# SiPD_Design.net
KiCad netlist of a schematic drawn in Altium Designer
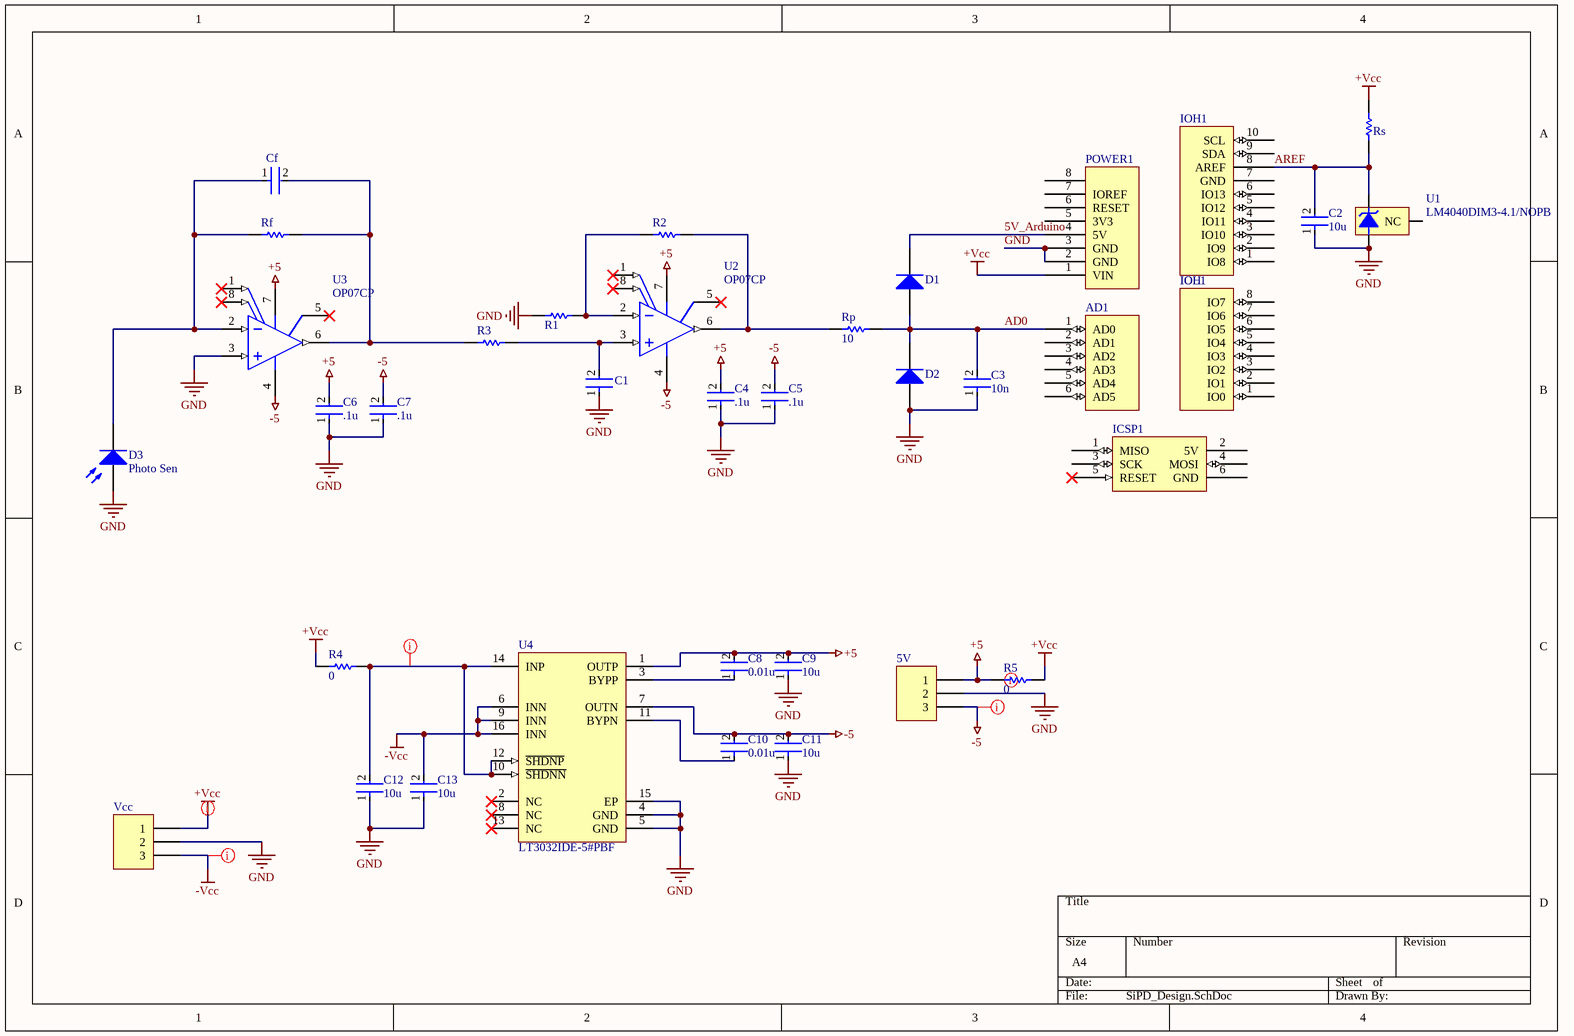
[diagram p0: SiPD_Design.SchDoc]

(export (version "E")
  (design (tool "Eeschema 10.0.6"))
  (components
    (comp (ref "5V")
      (value "5V")
      (footprint "HDR1X3")
      (description "Header, 3-Pin")
      (fields (field (name "PUBLISHER") "Altium Limited"))
      (libsource (lib "Miscellaneous Connectors") (part "Header 3"))
    )
    (comp (ref "AD1")
      (value "AD")
      (footprint "Header:Header 6x1 8.5mm")
      (libsource (lib "Header") (part "AD"))
    )
    (comp (ref "C1")
      (value "~")
      (footprint "FP-C0805C-DG-MFG")
      (description "CAP CER 10UF 10V X5R 0805")
      (fields (field (name "TOLERANCE") "10%") (field (name "MANUFACTURER PART NUMBER") "C0805C106K8PACTU"))
      (libsource (lib "Altium Content Vault") (part "11868f565c42a9108669ba33697ecf6"))
    )
    (comp (ref "C2")
      (value "10u")
      (footprint "FP-C0805C-DG-MFG")
      (description "CAP CER 10UF 10V X5R 0805")
      (fields (field (name "TOLERANCE") "10%") (field (name "MANUFACTURER PART NUMBER") "C0805C106K8PACTU"))
      (libsource (lib "Altium Content Vault") (part "11868f565c42a9108669ba33697ecf6"))
    )
    (comp (ref "C3")
      (value "10n")
      (footprint "FP-C0805C-DG-MFG")
      (description "CAP CER 10UF 10V X5R 0805")
      (fields (field (name "TOLERANCE") "10%") (field (name "MANUFACTURER PART NUMBER") "C0805C106K8PACTU"))
      (libsource (lib "Altium Content Vault") (part "11868f565c42a9108669ba33697ecf6"))
    )
    (comp (ref "C4")
      (value ".1u")
      (footprint "FP-C0805C-DG-MFG")
      (description "CAP CER 10UF 10V X5R 0805")
      (fields (field (name "TOLERANCE") "10%") (field (name "MANUFACTURER PART NUMBER") "C0805C106K8PACTU"))
      (libsource (lib "Altium Content Vault") (part "11868f565c42a9108669ba33697ecf6"))
    )
    (comp (ref "C5")
      (value ".1u")
      (footprint "FP-C0805C-DG-MFG")
      (description "CAP CER 10UF 10V X5R 0805")
      (fields (field (name "TOLERANCE") "10%") (field (name "MANUFACTURER PART NUMBER") "C0805C106K8PACTU"))
      (libsource (lib "Altium Content Vault") (part "11868f565c42a9108669ba33697ecf6"))
    )
    (comp (ref "C6")
      (value ".1u")
      (footprint "FP-C0805C-DG-MFG")
      (description "CAP CER 10UF 10V X5R 0805")
      (fields (field (name "TOLERANCE") "10%") (field (name "MANUFACTURER PART NUMBER") "C0805C106K8PACTU"))
      (libsource (lib "Altium Content Vault") (part "11868f565c42a9108669ba33697ecf6"))
    )
    (comp (ref "C7")
      (value ".1u")
      (footprint "FP-C0805C-DG-MFG")
      (description "CAP CER 10UF 10V X5R 0805")
      (fields (field (name "TOLERANCE") "10%") (field (name "MANUFACTURER PART NUMBER") "C0805C106K8PACTU"))
      (libsource (lib "Altium Content Vault") (part "11868f565c42a9108669ba33697ecf6"))
    )
    (comp (ref "C8")
      (value "0.01u")
      (footprint "FP-C0805C-DG-MFG")
      (description "CAP CER 10UF 10V X5R 0805")
      (fields (field (name "TOLERANCE") "10%") (field (name "MANUFACTURER PART NUMBER") "C0805C106K8PACTU"))
      (libsource (lib "Altium Content Vault") (part "11868f565c42a9108669ba33697ecf6"))
    )
    (comp (ref "C9")
      (value "10u")
      (footprint "FP-C0805C-DG-MFG")
      (description "CAP CER 10UF 10V X5R 0805")
      (fields (field (name "TOLERANCE") "10%") (field (name "MANUFACTURER PART NUMBER") "C0805C106K8PACTU"))
      (libsource (lib "Altium Content Vault") (part "11868f565c42a9108669ba33697ecf6"))
    )
    (comp (ref "C10")
      (value "0.01u")
      (footprint "FP-C0805C-DG-MFG")
      (description "CAP CER 10UF 10V X5R 0805")
      (fields (field (name "TOLERANCE") "10%") (field (name "MANUFACTURER PART NUMBER") "C0805C106K8PACTU"))
      (libsource (lib "Altium Content Vault") (part "11868f565c42a9108669ba33697ecf6"))
    )
    (comp (ref "C11")
      (value "10u")
      (footprint "FP-C0805C-DG-MFG")
      (description "CAP CER 10UF 10V X5R 0805")
      (fields (field (name "TOLERANCE") "10%") (field (name "MANUFACTURER PART NUMBER") "C0805C106K8PACTU"))
      (libsource (lib "Altium Content Vault") (part "11868f565c42a9108669ba33697ecf6"))
    )
    (comp (ref "C12")
      (value "10u")
      (footprint "FP-C0805C-DG-MFG")
      (description "CAP CER 10UF 10V X5R 0805")
      (fields (field (name "TOLERANCE") "10%") (field (name "MANUFACTURER PART NUMBER") "C0805C106K8PACTU"))
      (libsource (lib "Altium Content Vault") (part "11868f565c42a9108669ba33697ecf6"))
    )
    (comp (ref "C13")
      (value "10u")
      (footprint "FP-C0805C-DG-MFG")
      (description "CAP CER 10UF 10V X5R 0805")
      (fields (field (name "TOLERANCE") "10%") (field (name "MANUFACTURER PART NUMBER") "C0805C106K8PACTU"))
      (libsource (lib "Altium Content Vault") (part "11868f565c42a9108669ba33697ecf6"))
    )
    (comp (ref "Cf")
      (value "~")
      (footprint "FP-C0805C-DG-MFG")
      (description "CAP CER 10UF 10V X5R 0805")
      (fields (field (name "TOLERANCE") "10%") (field (name "MANUFACTURER PART NUMBER") "C0805C106K8PACTU"))
      (libsource (lib "Altium Content Vault") (part "11868f565c42a9108669ba33697ecf6"))
    )
    (comp (ref "D1")
      (value "Diode 1N4148")
      (footprint "DO-35")
      (description "High Conductance Fast Diode")
      (fields (field (name "PUBLISHER") "Altium Limited"))
      (libsource (lib "Miscellaneous Devices") (part "Diode 1N4148"))
    )
    (comp (ref "D2")
      (value "Diode 1N4148")
      (footprint "DO-35")
      (description "High Conductance Fast Diode")
      (fields (field (name "PUBLISHER") "Altium Limited"))
      (libsource (lib "Miscellaneous Devices") (part "Diode 1N4148"))
    )
    (comp (ref "D3")
      (value "Photo Sen")
      (footprint "PIN2")
      (description "Photosensitive Diode")
      (fields (field (name "PUBLISHER") "Altium Limited"))
      (libsource (lib "Miscellaneous Devices") (part "Photo Sen"))
    )
    (comp (ref "ICSP1") (value "ICSP") (footprint "ICSP") (libsource (lib "Header") (part "ICSP")))
    (comp (ref "IOH1")
      (value "IOH")
      (footprint "Header:Header 10x1 8.5mm")
      (libsource (lib "Header") (part "IOH"))
    )
    (comp (ref "IOL1") (value "IOL") (footprint "Header 8x1 8.5mm") (libsource (lib "Header") (part "IOL")))
    (comp (ref "POWER1")
      (value "POWER_UNO")
      (footprint "Header 8x1 8.5mm")
      (libsource (lib "Header") (part "POWER_UNO"))
    )
    (comp (ref "R1")
      (value "CRCW08050000Z0EA")
      (footprint "RESC2013X50X30LL20T20")
      (fields (field (name "MANUFACTURER") "Vishay Dale"))
      (libsource (lib "Altium Content Vault") (part "RES"))
    )
    (comp (ref "R2")
      (value "CRCW08050000Z0EA")
      (footprint "RESC2013X50X30LL20T20")
      (fields (field (name "MANUFACTURER") "Vishay Dale"))
      (libsource (lib "Altium Content Vault") (part "RES"))
    )
    (comp (ref "R3")
      (value "CRCW08050000Z0EA")
      (footprint "RESC2013X50X30LL20T20")
      (fields (field (name "MANUFACTURER") "Vishay Dale"))
      (libsource (lib "Altium Content Vault") (part "RES"))
    )
    (comp (ref "R4")
      (value "0")
      (footprint "RESC2013X50X30LL20T20")
      (fields (field (name "MANUFACTURER") "Vishay Dale") (field (name "PART NUMBER") "CRCW08050000Z0EA"))
      (libsource (lib "Altium Content Vault") (part "RES"))
    )
    (comp (ref "R5")
      (value "0")
      (footprint "RESC2013X50X30LL20T20")
      (fields (field (name "MANUFACTURER") "Vishay Dale") (field (name "PART NUMBER") "CRCW08050000Z0EA"))
      (libsource (lib "Altium Content Vault") (part "RES"))
    )
    (comp (ref "Rf")
      (value "~")
      (footprint "RESC2013X50X30LL20T20")
      (fields (field (name "MANUFACTURER") "Vishay Dale") (field (name "PART NUMBER") "CRCW08050000Z0EA"))
      (libsource (lib "Altium Content Vault") (part "RES"))
    )
    (comp (ref "Rp")
      (value "10")
      (footprint "RESC2013X50X30LL20T20")
      (fields (field (name "MANUFACTURER") "Vishay Dale") (field (name "PART NUMBER") "CRCW08050000Z0EA"))
      (libsource (lib "Altium Content Vault") (part "RES"))
    )
    (comp (ref "Rs")
      (value "CRCW08050000Z0EA")
      (footprint "RESC2013X50X30LL20T20")
      (fields (field (name "MANUFACTURER") "Vishay Dale"))
      (libsource (lib "Altium Content Vault") (part "RES"))
    )
    (comp (ref "U1")
      (value "LM4040DIM3-4.1/NOPB")
      (footprint "MF03A_N")
      (description "Precision Micropower Shunt Voltage Reference, 3-pin SOT-23, Pb-Free")
      (fields (field (name "MANUFACTURER") "National Semiconductor"))
      (libsource (lib "Altium Content Vault") (part "PM-REF-LM4040-SOT3"))
    )
    (comp (ref "U2")
      (value "OP07CP")
      (footprint "P0008A")
      (description "Low-Offset Voltage Operational Amplifier, 6 to 36 V, 0 to 70 degC, 8-pin DIP (P8), Pb-Free (RoHS)")
      (fields (field (name "MANUFACTURER") "Texas Instruments"))
      (libsource (lib "Altium Content Vault") (part "TI-OP07X-X8"))
    )
    (comp (ref "U3")
      (value "OP07CP")
      (footprint "P0008A")
      (description "Low-Offset Voltage Operational Amplifier, 6 to 36 V, 0 to 70 degC, 8-pin DIP (P8), Pb-Free (RoHS)")
      (fields (field (name "MANUFACTURER") "Texas Instruments"))
      (libsource (lib "Altium Content Vault") (part "TI-OP07X-X8"))
    )
    (comp (ref "U4")
      (value "LT3032IDE-5#PBF")
      (footprint "LT-DE14MA-14_V")
      (fields (field (name "MANUFACTURER") "Linear Technology"))
      (libsource (lib "Altium Content Vault") (part "LT-LT3032-DE14MA-14"))
    )
    (comp (ref "Vcc")
      (value "Vcc")
      (footprint "HDR1X3")
      (description "Header, 3-Pin")
      (fields (field (name "PUBLISHER") "Altium Limited"))
      (libsource (lib "Miscellaneous Connectors") (part "Header 3"))
    )
  )
  (nets
    (net (code "1") (name "+5") (class "Default")
      (node (ref "5V") (pin "1") (pinfunction "1_1") (pintype "passive"))
      (node (ref "C4") (pin "2") (pinfunction "2_2") (pintype "passive"))
      (node (ref "C6") (pin "2") (pinfunction "2_2") (pintype "passive"))
      (node (ref "C8") (pin "2") (pinfunction "2_2") (pintype "passive"))
      (node (ref "C9") (pin "2") (pinfunction "2_2") (pintype "passive"))
      (node (ref "R5") (pin "1") (pinfunction "1_1") (pintype "passive"))
      (node (ref "U2") (pin "7") (pinfunction "VCC+_7") (pintype "power_in"))
      (node (ref "U3") (pin "7") (pinfunction "VCC+_7") (pintype "power_in"))
      (node (ref "U4") (pin "1") (pinfunction "OUTP_1") (pintype "power_in"))
    )
    (net (code "2") (name "+Vcc") (class "Default")
      (node (ref "POWER1") (pin "1") (pinfunction "VIN_1") (pintype "power_in"))
      (node (ref "R4") (pin "1") (pinfunction "1_1") (pintype "passive"))
      (node (ref "R5") (pin "2") (pinfunction "2_2") (pintype "passive"))
      (node (ref "Rs") (pin "2") (pinfunction "2_2") (pintype "passive"))
      (node (ref "Vcc") (pin "1") (pinfunction "1_1") (pintype "passive"))
    )
    (net (code "3") (name "-5") (class "Default")
      (node (ref "5V") (pin "3") (pinfunction "3_3") (pintype "passive"))
      (node (ref "C10") (pin "2") (pinfunction "2_2") (pintype "passive"))
      (node (ref "C11") (pin "2") (pinfunction "2_2") (pintype "passive"))
      (node (ref "C5") (pin "2") (pinfunction "2_2") (pintype "passive"))
      (node (ref "C7") (pin "2") (pinfunction "2_2") (pintype "passive"))
      (node (ref "U2") (pin "4") (pinfunction "VCC-_4") (pintype "power_in"))
      (node (ref "U3") (pin "4") (pinfunction "VCC-_4") (pintype "power_in"))
      (node (ref "U4") (pin "7") (pinfunction "OUTN_7") (pintype "power_in"))
    )
    (net (code "4") (name "-Vcc") (class "Default")
      (node (ref "C13") (pin "2") (pinfunction "2_2") (pintype "passive"))
      (node (ref "U4") (pin "16") (pinfunction "INN_16") (pintype "power_in"))
      (node (ref "U4") (pin "6") (pinfunction "INN_6") (pintype "power_in"))
      (node (ref "U4") (pin "9") (pinfunction "INN_9") (pintype "power_in"))
      (node (ref "Vcc") (pin "3") (pinfunction "3_3") (pintype "passive"))
    )
    (net (code "5") (name "/5V_Arduino") (class "Default")
      (node (ref "D1") (pin "2") (pinfunction "K_2") (pintype "passive"))
      (node (ref "POWER1") (pin "4") (pinfunction "5V_4") (pintype "power_in"))
    )
    (net (code "6") (name "/AD0") (class "Default")
      (node (ref "AD1") (pin "1") (pinfunction "AD0_1") (pintype "bidirectional"))
      (node (ref "C3") (pin "2") (pinfunction "2_2") (pintype "passive"))
      (node (ref "D1") (pin "1") (pinfunction "A_1") (pintype "passive"))
      (node (ref "D2") (pin "2") (pinfunction "K_2") (pintype "passive"))
      (node (ref "Rp") (pin "2") (pinfunction "2_2") (pintype "passive"))
    )
    (net (code "7") (name "/AREF") (class "Default")
      (node (ref "C2") (pin "2") (pinfunction "2_2") (pintype "passive"))
      (node (ref "IOH1") (pin "8") (pinfunction "AREF_8") (pintype "passive"))
      (node (ref "Rs") (pin "1") (pinfunction "1_1") (pintype "passive"))
      (node (ref "U1") (pin "1") (pinfunction "+V_1") (pintype "passive"))
    )
    (net (code "8") (name "GND") (class "Default")
      (node (ref "5V") (pin "2") (pinfunction "2_2") (pintype "passive"))
      (node (ref "C1") (pin "1") (pinfunction "1_1") (pintype "passive"))
      (node (ref "C11") (pin "1") (pinfunction "1_1") (pintype "passive"))
      (node (ref "C12") (pin "1") (pinfunction "1_1") (pintype "passive"))
      (node (ref "C13") (pin "1") (pinfunction "1_1") (pintype "passive"))
      (node (ref "C2") (pin "1") (pinfunction "1_1") (pintype "passive"))
      (node (ref "C3") (pin "1") (pinfunction "1_1") (pintype "passive"))
      (node (ref "C4") (pin "1") (pinfunction "1_1") (pintype "passive"))
      (node (ref "C5") (pin "1") (pinfunction "1_1") (pintype "passive"))
      (node (ref "C6") (pin "1") (pinfunction "1_1") (pintype "passive"))
      (node (ref "C7") (pin "1") (pinfunction "1_1") (pintype "passive"))
      (node (ref "C9") (pin "1") (pinfunction "1_1") (pintype "passive"))
      (node (ref "D2") (pin "1") (pinfunction "A_1") (pintype "passive"))
      (node (ref "D3") (pin "1") (pinfunction "A_1") (pintype "passive"))
      (node (ref "POWER1") (pin "2") (pinfunction "GND_2") (pintype "power_in"))
      (node (ref "POWER1") (pin "3") (pinfunction "GND_3") (pintype "power_in"))
      (node (ref "R1") (pin "1") (pinfunction "1_1") (pintype "passive"))
      (node (ref "U1") (pin "2") (pinfunction "-V_2") (pintype "passive"))
      (node (ref "U3") (pin "3") (pinfunction "IN+_3") (pintype "input"))
      (node (ref "U4") (pin "15") (pinfunction "EP_15") (pintype "power_in"))
      (node (ref "U4") (pin "4") (pinfunction "GND_4") (pintype "power_in"))
      (node (ref "U4") (pin "5") (pinfunction "GND_5") (pintype "power_in"))
      (node (ref "Vcc") (pin "2") (pinfunction "2_2") (pintype "passive"))
    )
    (net (code "9") (name "Net-(D3-K)") (class "Default")
      (node (ref "Cf") (pin "1") (pinfunction "1_1") (pintype "passive"))
      (node (ref "D3") (pin "2") (pinfunction "K_2") (pintype "passive"))
      (node (ref "Rf") (pin "1") (pinfunction "1_1") (pintype "passive"))
      (node (ref "U3") (pin "2") (pinfunction "IN-_2") (pintype "input"))
    )
    (net (code "10") (name "Net-(U2-IN+)") (class "Default")
      (node (ref "C1") (pin "2") (pinfunction "2_2") (pintype "passive"))
      (node (ref "R3") (pin "2") (pinfunction "2_2") (pintype "passive"))
      (node (ref "U2") (pin "3") (pinfunction "IN+_3") (pintype "input"))
    )
    (net (code "11") (name "Net-(U2-IN-)") (class "Default")
      (node (ref "R1") (pin "2") (pinfunction "2_2") (pintype "passive"))
      (node (ref "R2") (pin "1") (pinfunction "1_1") (pintype "passive"))
      (node (ref "U2") (pin "2") (pinfunction "IN-_2") (pintype "input"))
    )
    (net (code "12") (name "Net-(U2-OUT)") (class "Default")
      (node (ref "R2") (pin "2") (pinfunction "2_2") (pintype "passive"))
      (node (ref "Rp") (pin "1") (pinfunction "1_1") (pintype "passive"))
      (node (ref "U2") (pin "6") (pinfunction "OUT_6") (pintype "output"))
    )
    (net (code "13") (name "Net-(U3-OUT)") (class "Default")
      (node (ref "Cf") (pin "2") (pinfunction "2_2") (pintype "passive"))
      (node (ref "R3") (pin "1") (pinfunction "1_1") (pintype "passive"))
      (node (ref "Rf") (pin "2") (pinfunction "2_2") (pintype "passive"))
      (node (ref "U3") (pin "6") (pinfunction "OUT_6") (pintype "output"))
    )
    (net (code "14") (name "Net-(U4-BYPN)") (class "Default")
      (node (ref "C10") (pin "1") (pinfunction "1_1") (pintype "passive"))
      (node (ref "U4") (pin "11") (pinfunction "BYPN_11") (pintype "passive"))
    )
    (net (code "15") (name "Net-(U4-BYPP)") (class "Default")
      (node (ref "C8") (pin "1") (pinfunction "1_1") (pintype "passive"))
      (node (ref "U4") (pin "3") (pinfunction "BYPP_3") (pintype "passive"))
    )
    (net (code "16") (name "Net-(U4-INP)") (class "Default")
      (node (ref "C12") (pin "2") (pinfunction "2_2") (pintype "passive"))
      (node (ref "R4") (pin "2") (pinfunction "2_2") (pintype "passive"))
      (node (ref "U4") (pin "10") (pinfunction "~{SHDNN}_10") (pintype "input"))
      (node (ref "U4") (pin "12") (pinfunction "~{SHDNP}_12") (pintype "input"))
      (node (ref "U4") (pin "14") (pinfunction "INP_14") (pintype "power_in"))
    )
    (net (code "17") (name "unconnected-(AD1-AD1-Pad2)") (class "Default")
      (node (ref "AD1") (pin "2") (pinfunction "AD1_2") (pintype "bidirectional"))
    )
    (net (code "18") (name "unconnected-(AD1-AD2-Pad3)") (class "Default")
      (node (ref "AD1") (pin "3") (pinfunction "AD2_3") (pintype "bidirectional"))
    )
    (net (code "19") (name "unconnected-(AD1-AD3-Pad4)") (class "Default")
      (node (ref "AD1") (pin "4") (pinfunction "AD3_4") (pintype "bidirectional"))
    )
    (net (code "20") (name "unconnected-(AD1-AD4-Pad5)") (class "Default")
      (node (ref "AD1") (pin "5") (pinfunction "AD4_5") (pintype "bidirectional"))
    )
    (net (code "21") (name "unconnected-(AD1-AD5-Pad6)") (class "Default")
      (node (ref "AD1") (pin "6") (pinfunction "AD5_6") (pintype "bidirectional"))
    )
    (net (code "22") (name "unconnected-(ICSP1-5V-Pad2)") (class "Default")
      (node (ref "ICSP1") (pin "2") (pinfunction "5V_2") (pintype "power_in"))
    )
    (net (code "23") (name "unconnected-(ICSP1-GND-Pad6)") (class "Default")
      (node (ref "ICSP1") (pin "6") (pinfunction "GND_6") (pintype "power_in"))
    )
    (net (code "24") (name "unconnected-(ICSP1-MISO-Pad1)") (class "Default")
      (node (ref "ICSP1") (pin "1") (pinfunction "MISO_1") (pintype "bidirectional"))
    )
    (net (code "25") (name "unconnected-(ICSP1-MOSI-Pad4)") (class "Default")
      (node (ref "ICSP1") (pin "4") (pinfunction "MOSI_4") (pintype "bidirectional"))
    )
    (net (code "26") (name "unconnected-(ICSP1-RESET-Pad5)") (class "Default")
      (node (ref "ICSP1") (pin "5") (pinfunction "RESET_5") (pintype "input+no_connect"))
    )
    (net (code "27") (name "unconnected-(ICSP1-SCK-Pad3)") (class "Default")
      (node (ref "ICSP1") (pin "3") (pinfunction "SCK_3") (pintype "bidirectional"))
    )
    (net (code "28") (name "unconnected-(IOH1-GND-Pad7)") (class "Default")
      (node (ref "IOH1") (pin "7") (pinfunction "GND_7") (pintype "power_in"))
    )
    (net (code "29") (name "unconnected-(IOH1-IO8-Pad1)") (class "Default")
      (node (ref "IOH1") (pin "1") (pinfunction "IO8_1") (pintype "bidirectional"))
    )
    (net (code "30") (name "unconnected-(IOH1-IO9-Pad2)") (class "Default")
      (node (ref "IOH1") (pin "2") (pinfunction "IO9_2") (pintype "bidirectional"))
    )
    (net (code "31") (name "unconnected-(IOH1-IO10-Pad3)") (class "Default")
      (node (ref "IOH1") (pin "3") (pinfunction "IO10_3") (pintype "bidirectional"))
    )
    (net (code "32") (name "unconnected-(IOH1-IO11-Pad4)") (class "Default")
      (node (ref "IOH1") (pin "4") (pinfunction "IO11_4") (pintype "bidirectional"))
    )
    (net (code "33") (name "unconnected-(IOH1-IO12-Pad5)") (class "Default")
      (node (ref "IOH1") (pin "5") (pinfunction "IO12_5") (pintype "bidirectional"))
    )
    (net (code "34") (name "unconnected-(IOH1-IO13-Pad6)") (class "Default")
      (node (ref "IOH1") (pin "6") (pinfunction "IO13_6") (pintype "bidirectional"))
    )
    (net (code "35") (name "unconnected-(IOH1-SCL-Pad10)") (class "Default")
      (node (ref "IOH1") (pin "10") (pinfunction "SCL_10") (pintype "bidirectional"))
    )
    (net (code "36") (name "unconnected-(IOH1-SDA-Pad9)") (class "Default")
      (node (ref "IOH1") (pin "9") (pinfunction "SDA_9") (pintype "bidirectional"))
    )
    (net (code "37") (name "unconnected-(IOL1-IO0-Pad1)") (class "Default")
      (node (ref "IOL1") (pin "1") (pinfunction "IO0_1") (pintype "bidirectional"))
    )
    (net (code "38") (name "unconnected-(IOL1-IO1-Pad2)") (class "Default")
      (node (ref "IOL1") (pin "2") (pinfunction "IO1_2") (pintype "bidirectional"))
    )
    (net (code "39") (name "unconnected-(IOL1-IO2-Pad3)") (class "Default")
      (node (ref "IOL1") (pin "3") (pinfunction "IO2_3") (pintype "bidirectional"))
    )
    (net (code "40") (name "unconnected-(IOL1-IO3-Pad4)") (class "Default")
      (node (ref "IOL1") (pin "4") (pinfunction "IO3_4") (pintype "bidirectional"))
    )
    (net (code "41") (name "unconnected-(IOL1-IO4-Pad5)") (class "Default")
      (node (ref "IOL1") (pin "5") (pinfunction "IO4_5") (pintype "bidirectional"))
    )
    (net (code "42") (name "unconnected-(IOL1-IO5-Pad6)") (class "Default")
      (node (ref "IOL1") (pin "6") (pinfunction "IO5_6") (pintype "bidirectional"))
    )
    (net (code "43") (name "unconnected-(IOL1-IO6-Pad7)") (class "Default")
      (node (ref "IOL1") (pin "7") (pinfunction "IO6_7") (pintype "bidirectional"))
    )
    (net (code "44") (name "unconnected-(IOL1-IO7-Pad8)") (class "Default")
      (node (ref "IOL1") (pin "8") (pinfunction "IO7_8") (pintype "bidirectional"))
    )
    (net (code "45") (name "unconnected-(POWER1-3V3-Pad5)") (class "Default")
      (node (ref "POWER1") (pin "5") (pinfunction "3V3_5") (pintype "power_in"))
    )
    (net (code "46") (name "unconnected-(POWER1-IOREF-Pad7)") (class "Default")
      (node (ref "POWER1") (pin "7") (pinfunction "IOREF_7") (pintype "power_in"))
    )
    (net (code "47") (name "unconnected-(POWER1-Pad8)") (class "Default")
      (node (ref "POWER1") (pin "8") (pintype "passive"))
    )
    (net (code "48") (name "unconnected-(POWER1-RESET-Pad6)") (class "Default")
      (node (ref "POWER1") (pin "6") (pinfunction "RESET_6") (pintype "passive"))
    )
    (net (code "49") (name "unconnected-(U1-NC-Pad3)") (class "Default")
      (node (ref "U1") (pin "3") (pinfunction "NC_3") (pintype "passive"))
    )
    (net (code "50") (name "unconnected-(U2-NC-Pad5)") (class "Default")
      (node (ref "U2") (pin "5") (pinfunction "NC_5") (pintype "passive+no_connect"))
    )
    (net (code "51") (name "unconnected-(U2-OFFSET_N1-Pad1)") (class "Default")
      (node (ref "U2") (pin "1") (pinfunction "OFFSET_N1_1") (pintype "input+no_connect"))
    )
    (net (code "52") (name "unconnected-(U2-OFFSET_N2-Pad8)") (class "Default")
      (node (ref "U2") (pin "8") (pinfunction "OFFSET_N2_8") (pintype "input+no_connect"))
    )
    (net (code "53") (name "unconnected-(U3-NC-Pad5)") (class "Default")
      (node (ref "U3") (pin "5") (pinfunction "NC_5") (pintype "passive+no_connect"))
    )
    (net (code "54") (name "unconnected-(U3-OFFSET_N1-Pad1)") (class "Default")
      (node (ref "U3") (pin "1") (pinfunction "OFFSET_N1_1") (pintype "input+no_connect"))
    )
    (net (code "55") (name "unconnected-(U3-OFFSET_N2-Pad8)") (class "Default")
      (node (ref "U3") (pin "8") (pinfunction "OFFSET_N2_8") (pintype "input+no_connect"))
    )
    (net (code "56") (name "unconnected-(U4-NC-Pad2)") (class "Default")
      (node (ref "U4") (pin "2") (pinfunction "NC_2") (pintype "passive+no_connect"))
    )
    (net (code "57") (name "unconnected-(U4-NC-Pad8)") (class "Default")
      (node (ref "U4") (pin "8") (pinfunction "NC_8") (pintype "passive+no_connect"))
    )
    (net (code "58") (name "unconnected-(U4-NC-Pad13)") (class "Default")
      (node (ref "U4") (pin "13") (pinfunction "NC_13") (pintype "passive+no_connect"))
    )
  )
)
